# Debugging_Leds.net
KiCad netlist of a schematic drawn in Altium Designer
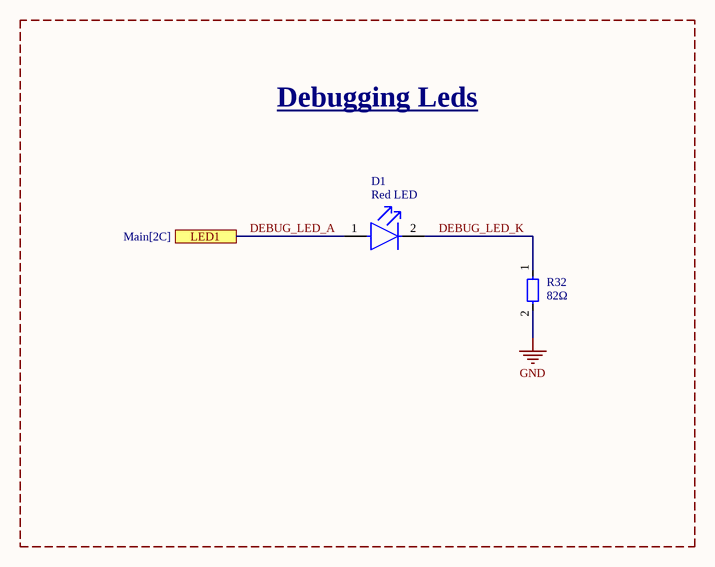
[diagram p0: Debugging_Leds.SchDoc]

(export (version "E")
  (design (tool "Eeschema 10.0.6"))
  (components
    (comp (ref "D1")
      (value "Red LED")
      (footprint "FP-SML-LX0805SRC-TR-MFG")
      (description "LED RED CLEAR SMD SML-LX0805SRC-TR")
      (libsource (lib "Altium Content Vault") (part "ab1c01a81903e929fc6c44469aada92"))
    )
    (comp (ref "R32")
      (value "82Ω")
      (footprint "RES_0603")
      (description "RES  82R 1% 0603")
      (fields (field (name "Comment") "82R"))
      (libsource (lib "Passive_Components") (part "Generic R"))
    )
  )
  (nets
    (net (code "1") (name "/DEBUG_LED_A") (class "Default")
      (node (ref "D1") (pin "1") (pinfunction "A_1") (pintype "passive"))
    )
    (net (code "2") (name "/DEBUG_LED_K") (class "Default")
      (node (ref "D1") (pin "2") (pinfunction "C_2") (pintype "passive"))
      (node (ref "R32") (pin "1") (pinfunction "1_1") (pintype "passive"))
    )
    (net (code "3") (name "GND") (class "Default")
      (node (ref "R32") (pin "2") (pinfunction "2_2") (pintype "passive"))
    )
  )
)
